# blink1mk2_v2d5_usbpcb.net
KiCad netlist of a schematic drawn in EAGLE
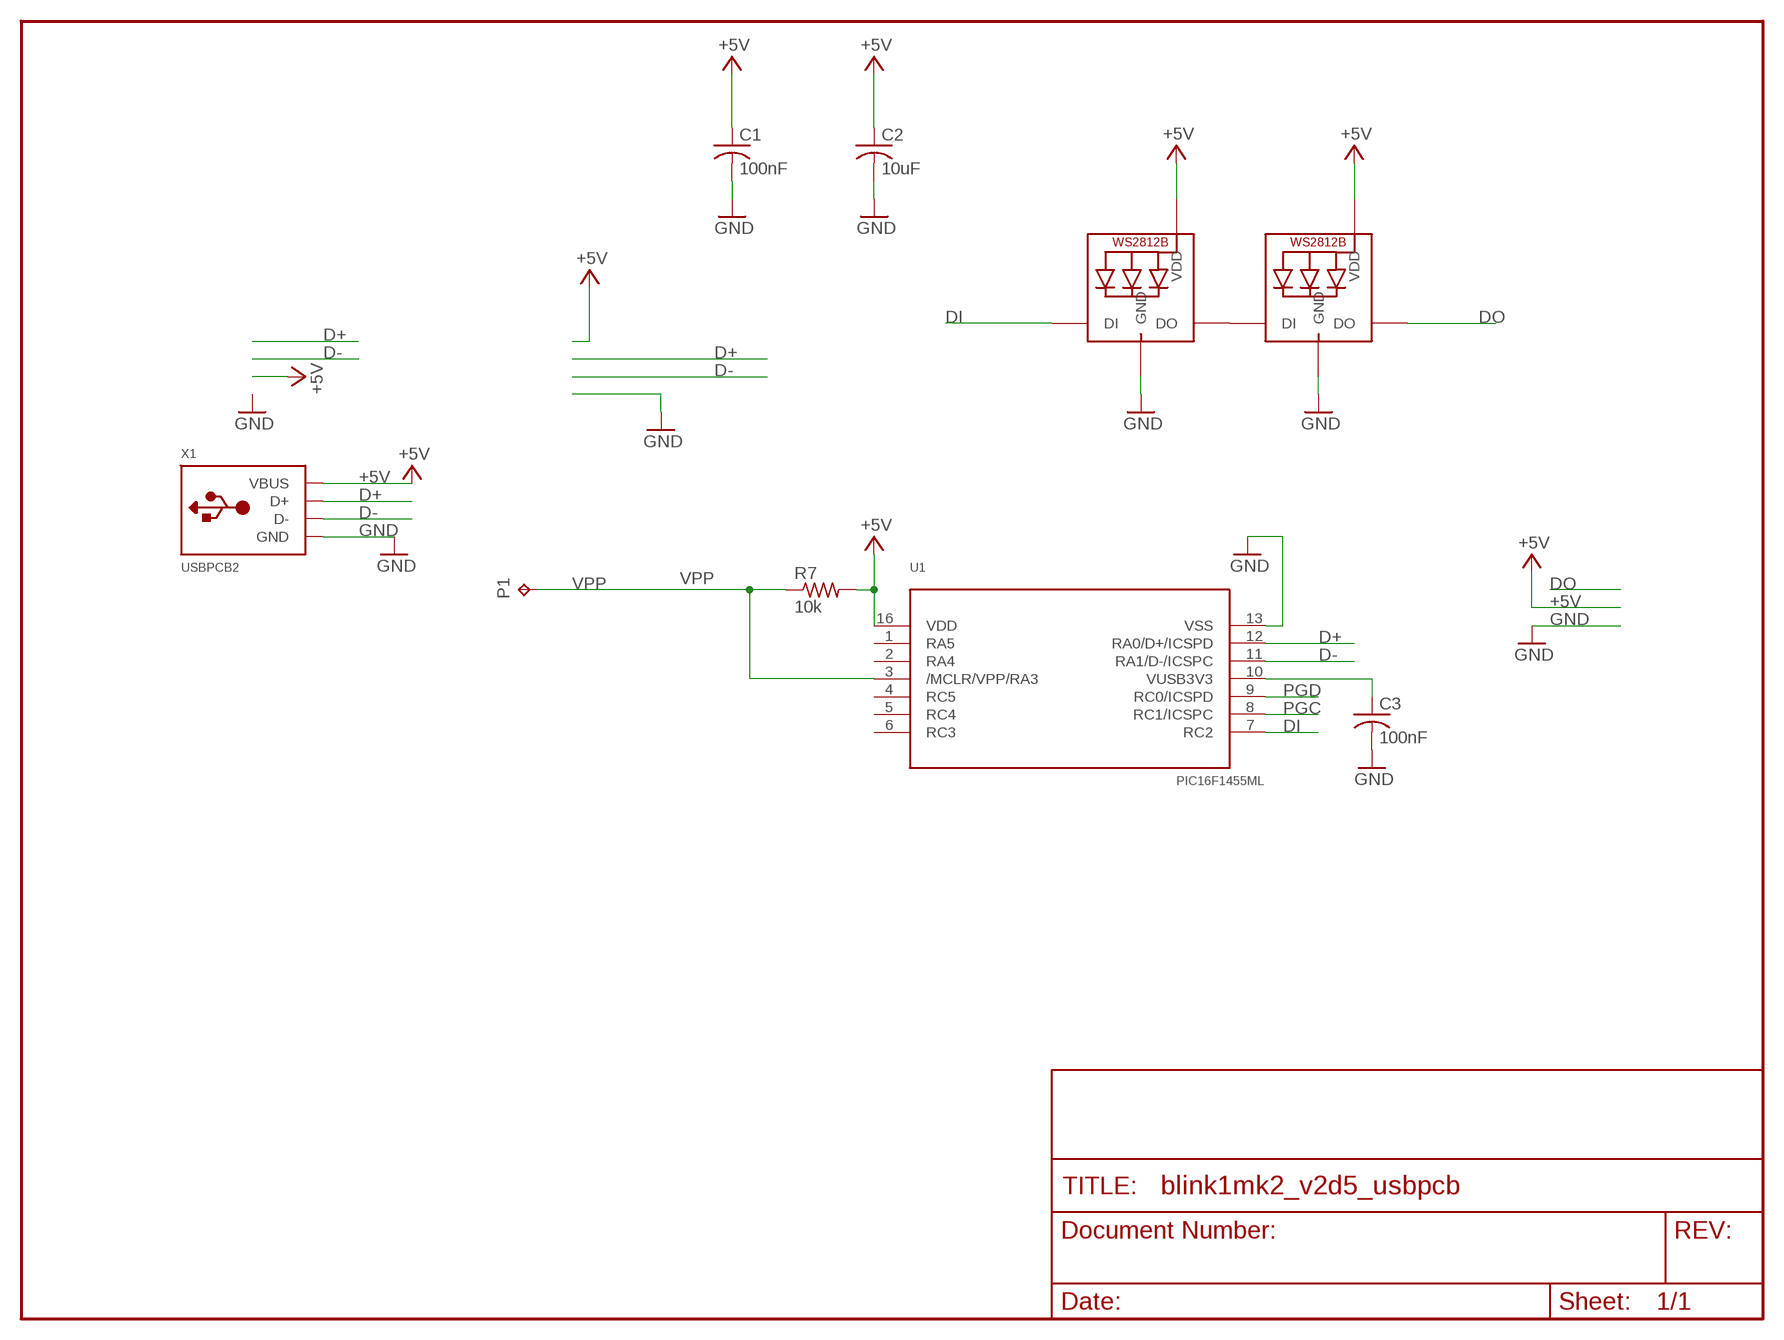
[diagram p0: schematic, sheet 1]

(export (version "E")
  (design (tool "Eeschema 10.0.6"))
  (components
    (comp (ref "C1")
      (value "100nF")
      (footprint "eagle-import:C0402")
      (libsource (lib "eagle-import") (part "C-USC0402"))
    )
    (comp (ref "C2")
      (value "10uF")
      (footprint "eagle-import:C0402")
      (libsource (lib "eagle-import") (part "C-USC0402"))
    )
    (comp (ref "C3")
      (value "100nF")
      (footprint "eagle-import:C0402")
      (libsource (lib "eagle-import") (part "C-USC0402"))
    )
    (comp (ref "LED1")
      (value "WS2812B4020SIDE")
      (footprint "eagle-import:SK6812-SIDE")
      (libsource (lib "eagle-import") (part "WS2812B4020SIDE"))
    )
    (comp (ref "LED2")
      (value "WS2812B4020SIDE")
      (footprint "eagle-import:SK6812-SIDE")
      (libsource (lib "eagle-import") (part "WS2812B4020SIDE"))
    )
    (comp (ref "P1")
      (value "TPTP11SQ")
      (footprint "eagle-import:TP11SQ")
      (libsource (lib "eagle-import") (part "TPTP11SQ"))
    )
    (comp (ref "R7")
      (value "10k")
      (footprint "eagle-import:R0402")
      (libsource (lib "eagle-import") (part "R-US_R0402"))
    )
    (comp (ref "U1")
      (value "PIC16F1455ML")
      (footprint "eagle-import:QFN16_4X4")
      (libsource (lib "eagle-import") (part "PIC16F1455ML"))
    )
    (comp (ref "X1")
      (value "USBPCB2")
      (footprint "eagle-import:USB-A-PCB-2")
      (libsource (lib "eagle-import") (part "USBPCB2"))
    )
  )
  (nets
    (net (code "1") (name "+5V") (class "Default")
      (node (ref "C1") (pin "1") (pinfunction "1_1") (pintype "passive"))
      (node (ref "C2") (pin "1") (pinfunction "1_1") (pintype "passive"))
      (node (ref "LED1") (pin "1-VDD") (pinfunction "VDD_1-VDD") (pintype "power_in"))
      (node (ref "LED2") (pin "1-VDD") (pinfunction "VDD_1-VDD") (pintype "power_in"))
      (node (ref "R7") (pin "2") (pinfunction "2_2") (pintype "passive"))
      (node (ref "U1") (pin "16") (pinfunction "VDD_16") (pintype "bidirectional"))
      (node (ref "X1") (pin "5V") (pinfunction "VBUS_5V") (pintype "power_in"))
    )
    (net (code "2") (name "/D+") (class "Default")
      (node (ref "U1") (pin "12") (pinfunction "RA0/D+/ICSPD_12") (pintype "bidirectional"))
      (node (ref "X1") (pin "USB_P") (pinfunction "D+_USB_P") (pintype "bidirectional"))
    )
    (net (code "3") (name "/D-") (class "Default")
      (node (ref "U1") (pin "11") (pinfunction "RA1/D-/ICSPC_11") (pintype "bidirectional"))
      (node (ref "X1") (pin "USB_M") (pinfunction "D-_USB_M") (pintype "bidirectional"))
    )
    (net (code "4") (name "/DI") (class "Default")
      (node (ref "LED1") (pin "4-DIN") (pinfunction "DI_4-DIN") (pintype "input"))
      (node (ref "U1") (pin "7") (pinfunction "RC2_7") (pintype "bidirectional"))
    )
    (net (code "5") (name "/DO") (class "Default")
      (node (ref "LED2") (pin "2-DOUT") (pinfunction "DO_2-DOUT") (pintype "output"))
    )
    (net (code "6") (name "/PGC") (class "Default")
      (node (ref "U1") (pin "8") (pinfunction "RC1/ICSPC_8") (pintype "bidirectional"))
    )
    (net (code "7") (name "/PGD") (class "Default")
      (node (ref "U1") (pin "9") (pinfunction "RC0/ICSPD_9") (pintype "bidirectional"))
    )
    (net (code "8") (name "/VPP") (class "Default")
      (node (ref "P1") (pin "TP") (pinfunction "TP_TP") (pintype "input"))
      (node (ref "R7") (pin "1") (pinfunction "1_1") (pintype "passive"))
      (node (ref "U1") (pin "3") (pinfunction "/MCLR/VPP/RA3_3") (pintype "bidirectional"))
    )
    (net (code "9") (name "GND") (class "Default")
      (node (ref "C1") (pin "2") (pinfunction "2_2") (pintype "passive"))
      (node (ref "C2") (pin "2") (pinfunction "2_2") (pintype "passive"))
      (node (ref "C3") (pin "2") (pinfunction "2_2") (pintype "passive"))
      (node (ref "LED1") (pin "3-GND") (pinfunction "GND_3-GND") (pintype "power_in"))
      (node (ref "LED2") (pin "3-GND") (pinfunction "GND_3-GND") (pintype "power_in"))
      (node (ref "U1") (pin "13") (pinfunction "VSS_13") (pintype "bidirectional"))
      (node (ref "X1") (pin "GND") (pinfunction "GND_GND") (pintype "power_in"))
    )
    (net (code "10") (name "Net-(LED1-DO)") (class "Default")
      (node (ref "LED1") (pin "2-DOUT") (pinfunction "DO_2-DOUT") (pintype "output"))
      (node (ref "LED2") (pin "4-DIN") (pinfunction "DI_4-DIN") (pintype "input"))
    )
    (net (code "11") (name "Net-(U1-VUSB3V3)") (class "Default")
      (node (ref "C3") (pin "1") (pinfunction "1_1") (pintype "passive"))
      (node (ref "U1") (pin "10") (pinfunction "VUSB3V3_10") (pintype "bidirectional"))
    )
    (net (code "12") (name "unconnected-(U1-RA4-Pad2)") (class "Default")
      (node (ref "U1") (pin "2") (pinfunction "RA4_2") (pintype "bidirectional"))
    )
    (net (code "13") (name "unconnected-(U1-RA5-Pad1)") (class "Default")
      (node (ref "U1") (pin "1") (pinfunction "RA5_1") (pintype "bidirectional"))
    )
    (net (code "14") (name "unconnected-(U1-RC3-Pad6)") (class "Default")
      (node (ref "U1") (pin "6") (pinfunction "RC3_6") (pintype "bidirectional"))
    )
    (net (code "15") (name "unconnected-(U1-RC4-Pad5)") (class "Default")
      (node (ref "U1") (pin "5") (pinfunction "RC4_5") (pintype "bidirectional"))
    )
    (net (code "16") (name "unconnected-(U1-RC5-Pad4)") (class "Default")
      (node (ref "U1") (pin "4") (pinfunction "RC5_4") (pintype "bidirectional"))
    )
  )
)
